# Tilt-NE555-A.net
KiCad netlist of a schematic drawn in EAGLE
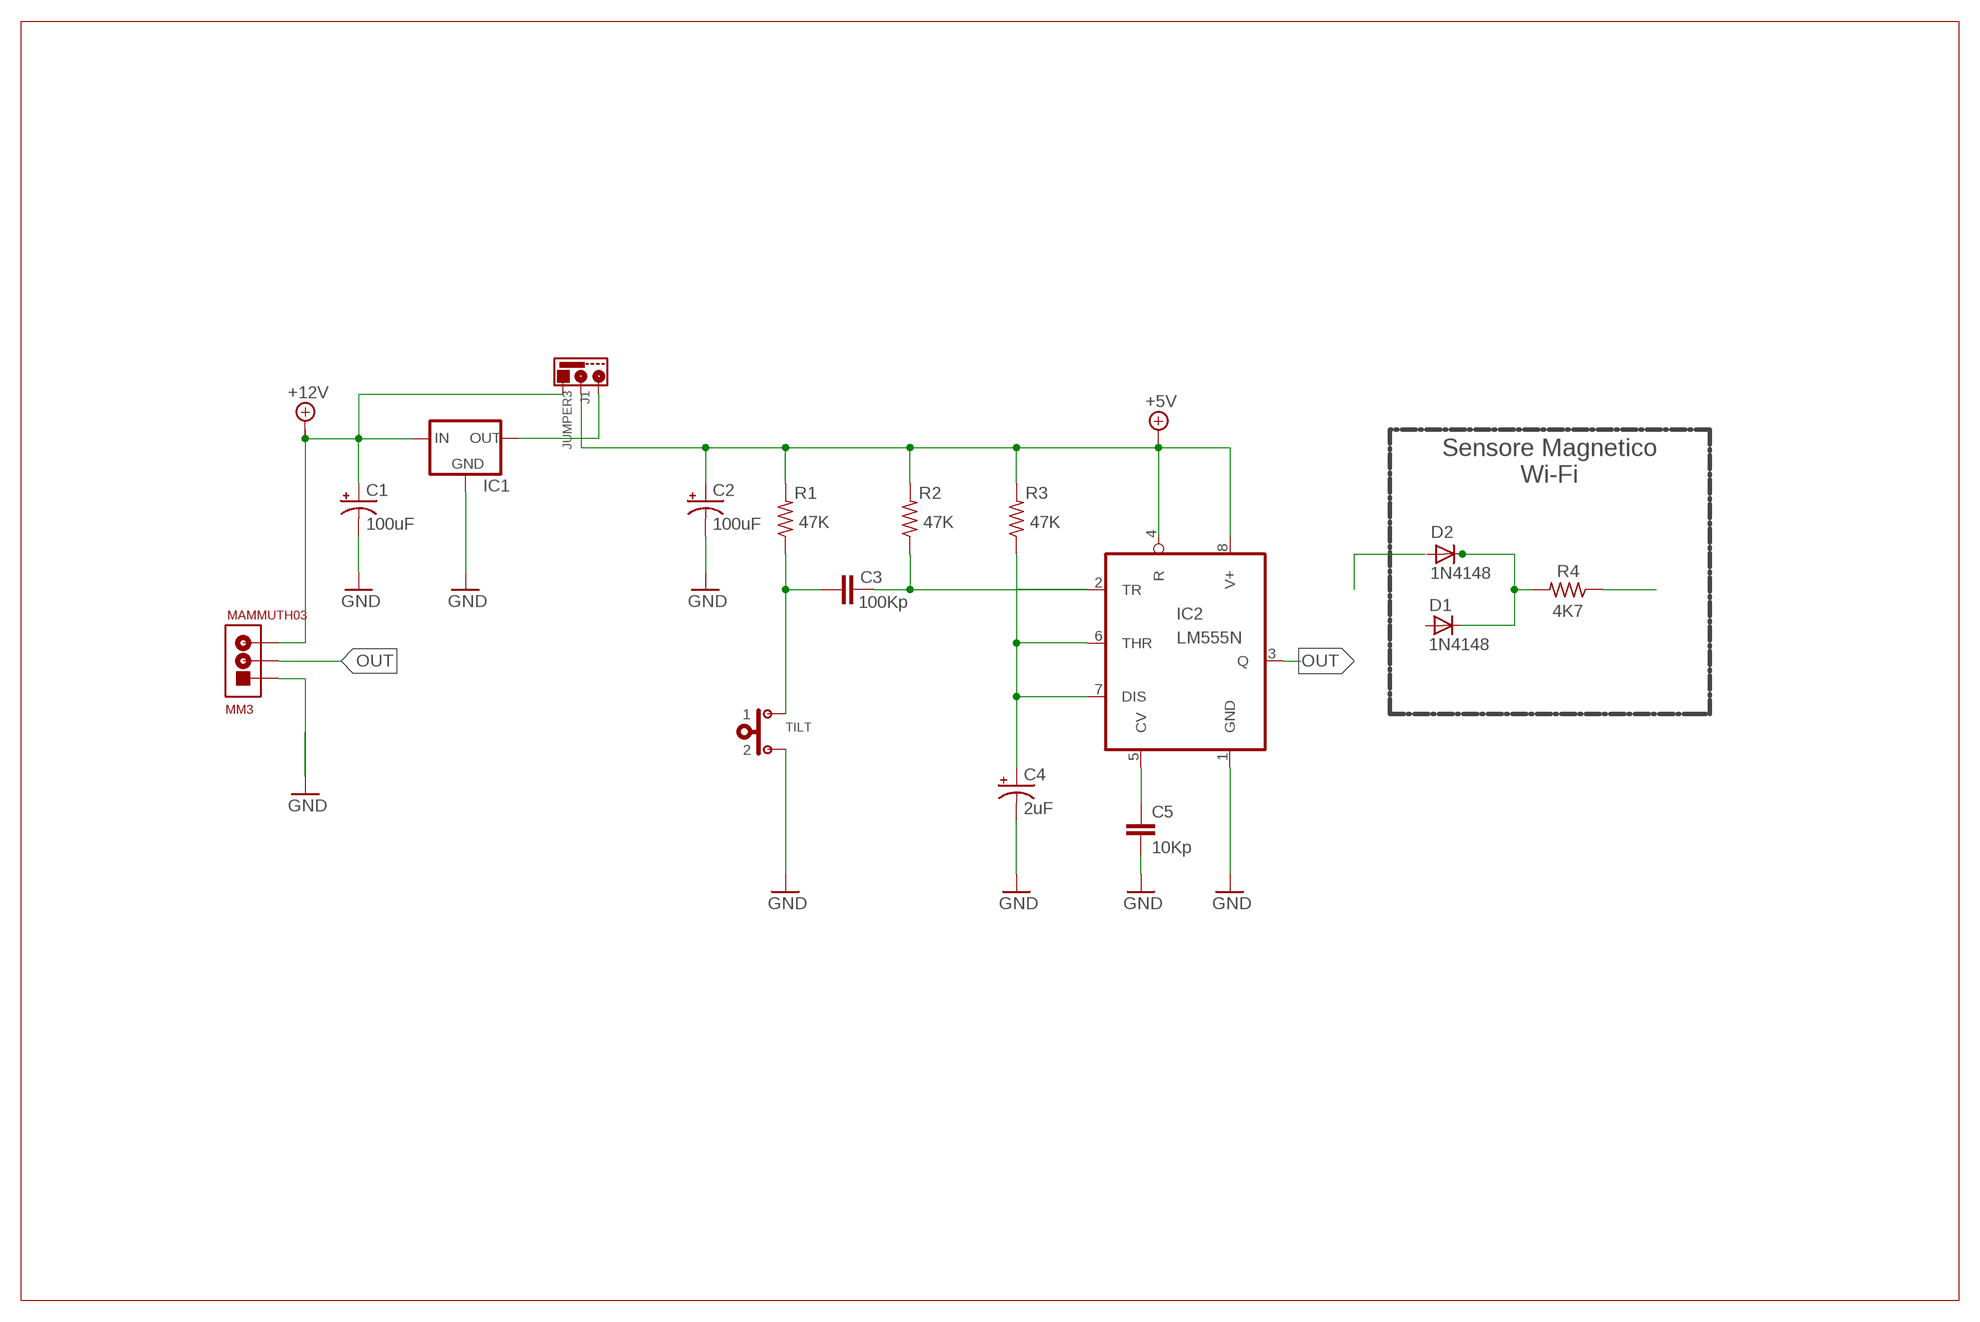
[diagram p0: schematic, sheet 1]

(export (version "E")
  (design (tool "Eeschema 10.0.6"))
  (components
    (comp (ref "C1")
      (value "100uF")
      (footprint "eagle-import:085CS_1AR")
      (libsource (lib "eagle-import") (part "CPOL-US085CS-1AR"))
    )
    (comp (ref "C2")
      (value "100uF")
      (footprint "eagle-import:085CS_1AR")
      (libsource (lib "eagle-import") (part "CPOL-US085CS-1AR"))
    )
    (comp (ref "C3")
      (value "100Kp")
      (footprint "eagle-import:C025-025X050")
      (libsource (lib "eagle-import") (part "C-EU025-025X050"))
    )
    (comp (ref "C4")
      (value "2uF")
      (footprint "eagle-import:085CS_1AR")
      (libsource (lib "eagle-import") (part "CPOL-US085CS-1AR"))
    )
    (comp (ref "C5")
      (value "10Kp")
      (footprint "eagle-import:C025-025X050")
      (libsource (lib "eagle-import") (part "C-EU025-025X050"))
    )
    (comp (ref "D1")
      (value "1N4148")
      (footprint "eagle-import:DO35-10")
      (libsource (lib "eagle-import") (part "1N4148DO35-10"))
    )
    (comp (ref "D2")
      (value "1N4148")
      (footprint "eagle-import:DO35-10")
      (libsource (lib "eagle-import") (part "1N4148DO35-10"))
    )
    (comp (ref "IC1")
      (value "78LXX")
      (footprint "eagle-import:78LXX")
      (libsource (lib "eagle-import") (part "78LXX"))
    )
    (comp (ref "IC2")
      (value "LM555N")
      (footprint "eagle-import:DIL08")
      (libsource (lib "eagle-import") (part "555NLM"))
    )
    (comp (ref "J1")
      (value "JUMPER3")
      (footprint "eagle-import:SIP03")
      (libsource (lib "eagle-import") (part "JUMPER3"))
    )
    (comp (ref "MM3")
      (value "MAMMUTH03")
      (footprint "eagle-import:MAMMUTH03")
      (libsource (lib "eagle-import") (part "MAMMUTH03"))
    )
    (comp (ref "R1")
      (value "47K")
      (footprint "eagle-import:0207_12")
      (libsource (lib "eagle-import") (part "R-US_0207/12"))
    )
    (comp (ref "R2")
      (value "47K")
      (footprint "eagle-import:0207_12")
      (libsource (lib "eagle-import") (part "R-US_0207/12"))
    )
    (comp (ref "R3")
      (value "47K")
      (footprint "eagle-import:0207_12")
      (libsource (lib "eagle-import") (part "R-US_0207/12"))
    )
    (comp (ref "R4")
      (value "4K7")
      (footprint "eagle-import:0207_12")
      (libsource (lib "eagle-import") (part "R-US_0207/12"))
    )
    (comp (ref "TILT")
      (value "PULSANTENO")
      (footprint "eagle-import:SIP02")
      (libsource (lib "eagle-import") (part "PULSANTENO"))
    )
  )
  (nets
    (net (code "1") (name "+5V") (class "Default")
      (node (ref "C2") (pin "+") (pinfunction "+_+") (pintype "passive"))
      (node (ref "IC2") (pin "4") (pinfunction "R_4") (pintype "input"))
      (node (ref "IC2") (pin "8") (pinfunction "V+_8") (pintype "power_in"))
      (node (ref "J1") (pin "1") (pinfunction "1_1") (pintype "bidirectional"))
      (node (ref "R1") (pin "2") (pinfunction "2_2") (pintype "passive"))
      (node (ref "R2") (pin "2") (pinfunction "2_2") (pintype "passive"))
      (node (ref "R3") (pin "2") (pinfunction "2_2") (pintype "passive"))
    )
    (net (code "2") (name "+12V") (class "Default")
      (node (ref "C1") (pin "+") (pinfunction "+_+") (pintype "passive"))
      (node (ref "IC1") (pin "IN") (pinfunction "IN_IN") (pintype "input"))
      (node (ref "J1") (pin "2") (pinfunction "2_2") (pintype "bidirectional"))
      (node (ref "MM3") (pin "P$3") (pinfunction "3_P$3") (pintype "bidirectional"))
    )
    (net (code "3") (name "GND") (class "Default")
      (node (ref "C1") (pin "-") (pinfunction "-_-") (pintype "passive"))
      (node (ref "C2") (pin "-") (pinfunction "-_-") (pintype "passive"))
      (node (ref "C4") (pin "-") (pinfunction "-_-") (pintype "passive"))
      (node (ref "C5") (pin "2") (pinfunction "2_2") (pintype "passive"))
      (node (ref "IC1") (pin "GND") (pinfunction "GND_GND") (pintype "input"))
      (node (ref "IC2") (pin "1") (pinfunction "GND_1") (pintype "power_in"))
      (node (ref "MM3") (pin "P$1") (pinfunction "1_P$1") (pintype "bidirectional"))
      (node (ref "TILT") (pin "2") (pinfunction "2_2") (pintype "bidirectional"))
    )
    (net (code "4") (name "Net-(C3-Pad1)") (class "Default")
      (node (ref "C3") (pin "1") (pinfunction "1_1") (pintype "passive"))
      (node (ref "R1") (pin "1") (pinfunction "1_1") (pintype "passive"))
      (node (ref "TILT") (pin "1") (pinfunction "1_1") (pintype "bidirectional"))
    )
    (net (code "5") (name "Net-(D1-PadC)") (class "Default")
      (node (ref "D1") (pin "C") (pinfunction "C_C") (pintype "passive"))
      (node (ref "D2") (pin "C") (pinfunction "C_C") (pintype "passive"))
      (node (ref "R4") (pin "2") (pinfunction "2_2") (pintype "passive"))
    )
    (net (code "6") (name "Net-(IC1-PadOUT)") (class "Default")
      (node (ref "IC1") (pin "OUT") (pinfunction "OUT_OUT") (pintype "passive"))
      (node (ref "J1") (pin "3") (pinfunction "3_3") (pintype "bidirectional"))
    )
    (net (code "7") (name "Net-(IC2-CV)") (class "Default")
      (node (ref "C5") (pin "1") (pinfunction "1_1") (pintype "passive"))
      (node (ref "IC2") (pin "5") (pinfunction "CV_5") (pintype "input"))
    )
    (net (code "8") (name "Net-(IC2-DIS)") (class "Default")
      (node (ref "C4") (pin "+") (pinfunction "+_+") (pintype "passive"))
      (node (ref "IC2") (pin "6") (pinfunction "THR_6") (pintype "input"))
      (node (ref "IC2") (pin "7") (pinfunction "DIS_7") (pintype "input"))
      (node (ref "R3") (pin "1") (pinfunction "1_1") (pintype "passive"))
    )
    (net (code "9") (name "Net-(IC2-TR)") (class "Default")
      (node (ref "C3") (pin "2") (pinfunction "2_2") (pintype "passive"))
      (node (ref "IC2") (pin "2") (pinfunction "TR_2") (pintype "input"))
      (node (ref "R2") (pin "1") (pinfunction "1_1") (pintype "passive"))
    )
    (net (code "10") (name "OUT") (class "Default")
      (node (ref "IC2") (pin "3") (pinfunction "Q_3") (pintype "output"))
      (node (ref "MM3") (pin "P$2") (pinfunction "2_P$2") (pintype "bidirectional"))
    )
    (net (code "11") (name "unconnected-(D1-PadA)") (class "Default")
      (node (ref "D1") (pin "A") (pinfunction "A_A") (pintype "passive"))
    )
    (net (code "12") (name "unconnected-(D2-PadA)") (class "Default")
      (node (ref "D2") (pin "A") (pinfunction "A_A") (pintype "passive"))
    )
    (net (code "13") (name "unconnected-(R4-Pad1)") (class "Default")
      (node (ref "R4") (pin "1") (pinfunction "1_1") (pintype "passive"))
    )
  )
)
